# ex_05.net
KiCad netlist of a schematic drawn in EAGLE
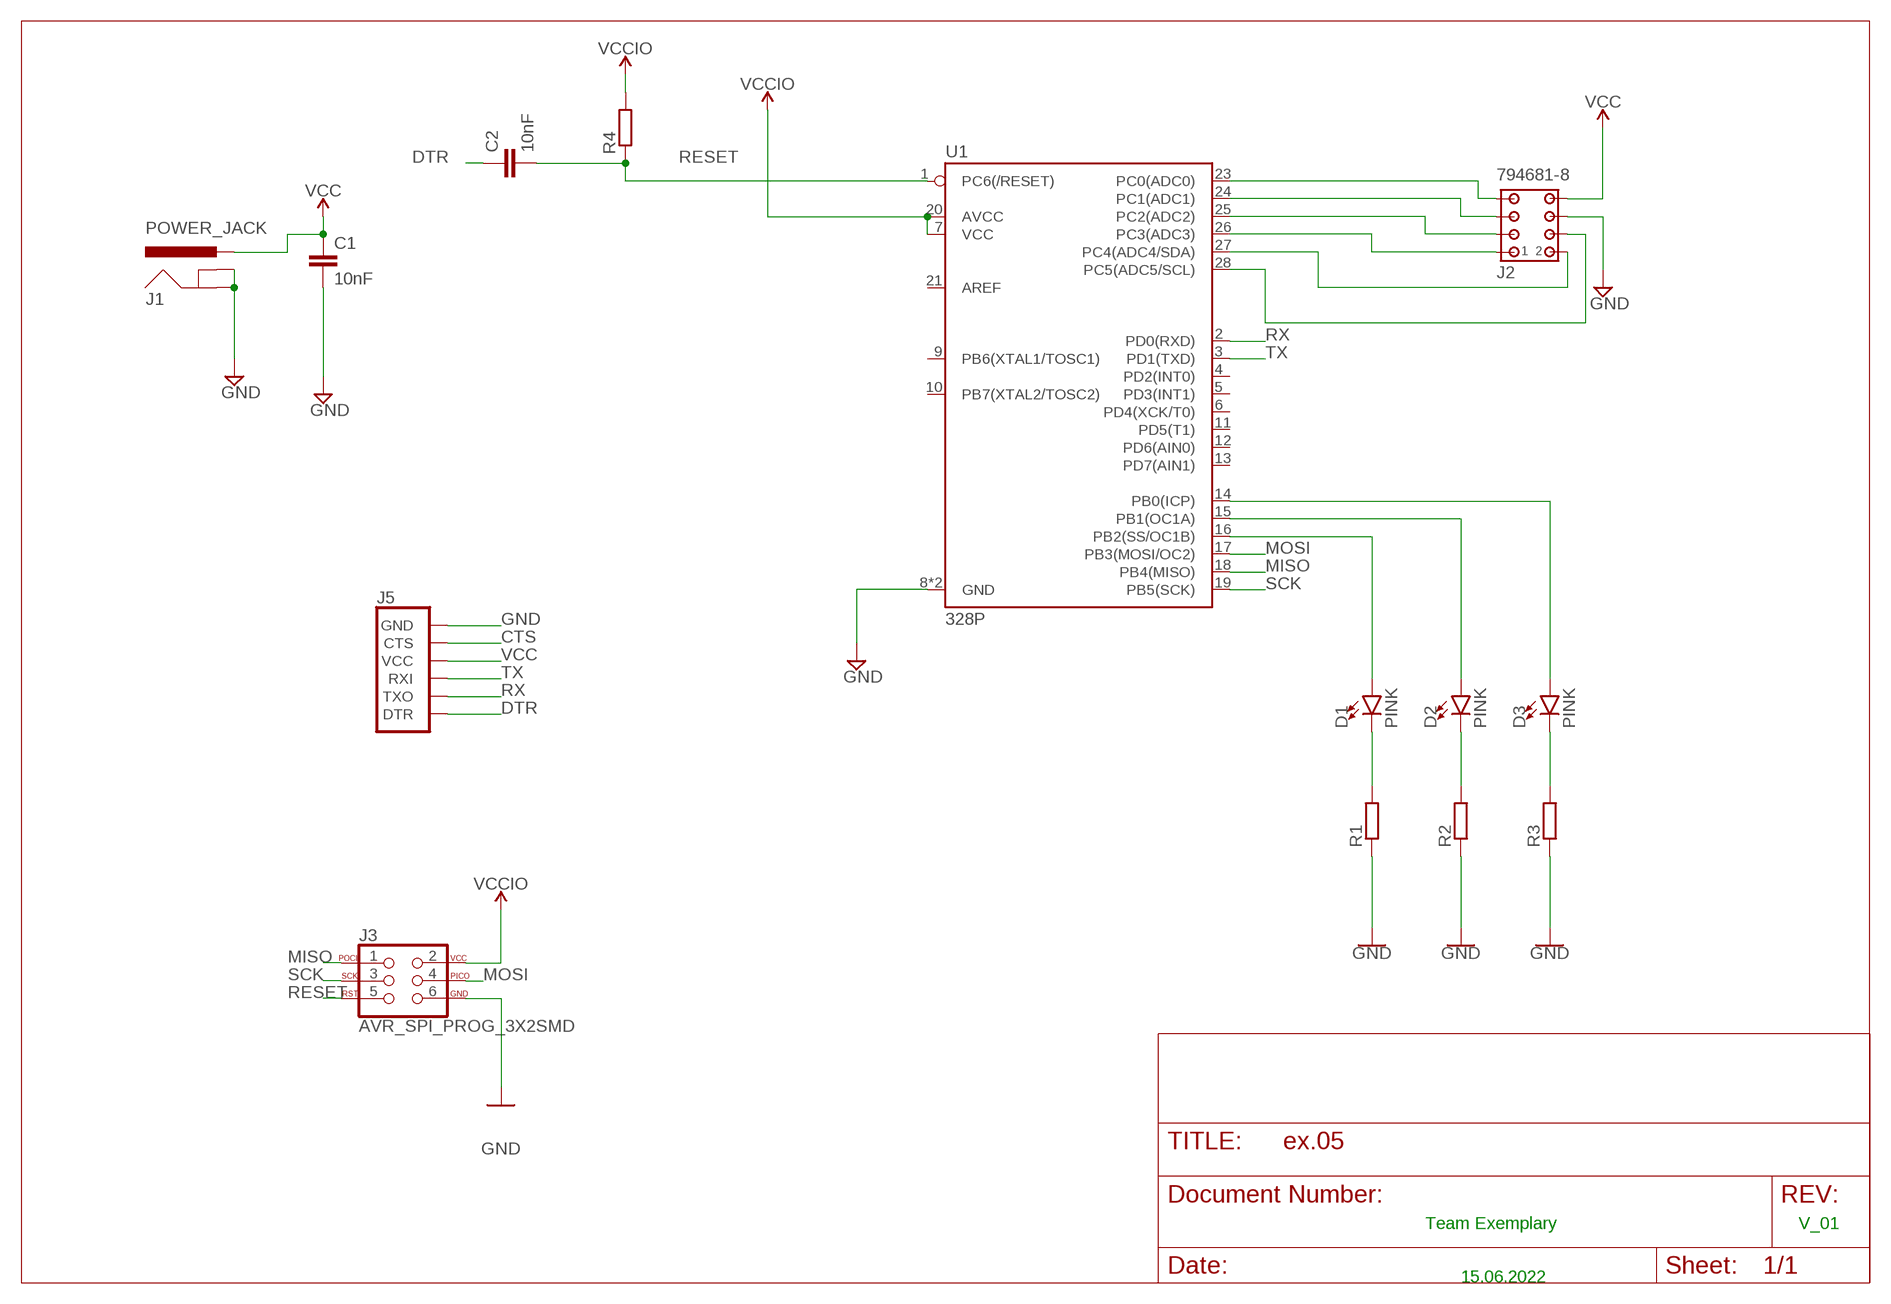
[diagram p0: schematic, sheet 1]

(export (version "E")
  (design (tool "Eeschema 10.0.6"))
  (components
    (comp (ref "C1")
      (value "10nF")
      (footprint "eagle-import:CAP-PTH-10MM")
      (libsource (lib "eagle-import") (part "10NF-PTH-10MM-10000V-1-%"))
    )
    (comp (ref "C2")
      (value "10nF")
      (footprint "eagle-import:CAP-PTH-10MM")
      (libsource (lib "eagle-import") (part "10NF-PTH-10MM-10000V-1-%"))
    )
    (comp (ref "D1")
      (value "PINK")
      (footprint "eagle-import:LED-1206")
      (libsource (lib "eagle-import") (part "LED-PINK1206"))
    )
    (comp (ref "D2")
      (value "PINK")
      (footprint "eagle-import:LED-1206")
      (libsource (lib "eagle-import") (part "LED-PINK1206"))
    )
    (comp (ref "D3")
      (value "PINK")
      (footprint "eagle-import:LED-1206")
      (libsource (lib "eagle-import") (part "LED-PINK1206"))
    )
    (comp (ref "J1")
      (value "POWER_JACK")
      (footprint "eagle-import:POWER_JACK_PTH")
      (libsource (lib "eagle-import") (part "POWER_JACK"))
    )
    (comp (ref "J2")
      (value "794681-8")
      (footprint "eagle-import:794681-8")
      (libsource (lib "eagle-import") (part "794681-8"))
    )
    (comp (ref "J3")
      (value "AVR_SPI_PROG_3X2SMD")
      (footprint "eagle-import:2X3_SMT_POSTS")
      (libsource (lib "eagle-import") (part "AVR_SPI_PROG_3X2SMD"))
    )
    (comp (ref "J5")
      (value "6_PIN_SERIAL_TARGETLOCK")
      (footprint "eagle-import:1X06_LOCK")
      (libsource (lib "eagle-import") (part "6_PIN_SERIAL_TARGETLOCK"))
    )
    (comp (ref "R1")
      (value "PMD")
      (footprint "eagle-import:PMD")
      (libsource (lib "eagle-import") (part "PMD"))
    )
    (comp (ref "R2")
      (value "PMD")
      (footprint "eagle-import:PMD")
      (libsource (lib "eagle-import") (part "PMD"))
    )
    (comp (ref "R3")
      (value "PMD")
      (footprint "eagle-import:PMD")
      (libsource (lib "eagle-import") (part "PMD"))
    )
    (comp (ref "R4")
      (value "PMD")
      (footprint "eagle-import:PMD")
      (libsource (lib "eagle-import") (part "PMD"))
    )
    (comp (ref "U1")
      (value "328P")
      (footprint "eagle-import:DIP28")
      (libsource (lib "eagle-import") (part "ATMEGA328P_PDIP"))
    )
  )
  (nets
    (net (code "1") (name "/CTS") (class "Default")
      (node (ref "J5") (pin "5") (pinfunction "CTS_5") (pintype "passive"))
    )
    (net (code "2") (name "/DTR") (class "Default")
      (node (ref "C2") (pin "1") (pinfunction "1_1") (pintype "passive"))
      (node (ref "J5") (pin "1") (pinfunction "DTR_1") (pintype "passive"))
    )
    (net (code "3") (name "/MISO") (class "Default")
      (node (ref "J3") (pin "1") (pinfunction "1_1") (pintype "passive"))
      (node (ref "U1") (pin "18") (pinfunction "PB4(MISO)_18") (pintype "bidirectional"))
    )
    (net (code "4") (name "/MOSI") (class "Default")
      (node (ref "J3") (pin "4") (pinfunction "4_4") (pintype "passive"))
      (node (ref "U1") (pin "17") (pinfunction "PB3(MOSI/OC2)_17") (pintype "bidirectional"))
    )
    (net (code "5") (name "/RESET") (class "Default")
      (node (ref "C2") (pin "2") (pinfunction "2_2") (pintype "passive"))
      (node (ref "J3") (pin "5") (pinfunction "5_5") (pintype "passive"))
      (node (ref "R4") (pin "2") (pinfunction "2_2") (pintype "passive"))
      (node (ref "U1") (pin "1") (pinfunction "PC6(/RESET)_1") (pintype "bidirectional"))
    )
    (net (code "6") (name "/RX") (class "Default")
      (node (ref "J5") (pin "3") (pinfunction "TXO_3") (pintype "passive"))
      (node (ref "U1") (pin "2") (pinfunction "PD0(RXD)_2") (pintype "bidirectional"))
    )
    (net (code "7") (name "/SCK") (class "Default")
      (node (ref "J3") (pin "3") (pinfunction "3_3") (pintype "passive"))
      (node (ref "U1") (pin "19") (pinfunction "PB5(SCK)_19") (pintype "bidirectional"))
    )
    (net (code "8") (name "/TX") (class "Default")
      (node (ref "J5") (pin "2") (pinfunction "RXI_2") (pintype "passive"))
      (node (ref "U1") (pin "3") (pinfunction "PD1(TXD)_3") (pintype "bidirectional"))
    )
    (net (code "9") (name "GND") (class "Default")
      (node (ref "C1") (pin "2") (pinfunction "2_2") (pintype "passive"))
      (node (ref "J1") (pin "GND") (pinfunction "GND_GND") (pintype "bidirectional"))
      (node (ref "J1") (pin "GNDBREAK") (pinfunction "GNDBREAK_GNDBREAK") (pintype "bidirectional"))
      (node (ref "J2") (pin "6") (pinfunction "6_6") (pintype "passive"))
      (node (ref "J3") (pin "6") (pinfunction "6_6") (pintype "passive"))
      (node (ref "J5") (pin "6") (pinfunction "GND_6") (pintype "passive"))
      (node (ref "R1") (pin "2") (pinfunction "2_2") (pintype "passive"))
      (node (ref "R2") (pin "2") (pinfunction "2_2") (pintype "passive"))
      (node (ref "R3") (pin "2") (pinfunction "2_2") (pintype "passive"))
      (node (ref "U1") (pin "22") (pinfunction "GND_22") (pintype "bidirectional"))
      (node (ref "U1") (pin "8") (pinfunction "GND_8") (pintype "bidirectional"))
    )
    (net (code "10") (name "Net-(D1-PadC)") (class "Default")
      (node (ref "D1") (pin "C") (pinfunction "C_C") (pintype "passive"))
      (node (ref "R1") (pin "1") (pinfunction "1_1") (pintype "passive"))
    )
    (net (code "11") (name "Net-(D2-PadC)") (class "Default")
      (node (ref "D2") (pin "C") (pinfunction "C_C") (pintype "passive"))
      (node (ref "R2") (pin "1") (pinfunction "1_1") (pintype "passive"))
    )
    (net (code "12") (name "Net-(D3-PadC)") (class "Default")
      (node (ref "D3") (pin "C") (pinfunction "C_C") (pintype "passive"))
      (node (ref "R3") (pin "1") (pinfunction "1_1") (pintype "passive"))
    )
    (net (code "13") (name "Net-(U1-PB0(ICP))") (class "Default")
      (node (ref "D3") (pin "A") (pinfunction "A_A") (pintype "passive"))
      (node (ref "U1") (pin "14") (pinfunction "PB0(ICP)_14") (pintype "bidirectional"))
    )
    (net (code "14") (name "Net-(U1-PB1(OC1A))") (class "Default")
      (node (ref "D2") (pin "A") (pinfunction "A_A") (pintype "passive"))
      (node (ref "U1") (pin "15") (pinfunction "PB1(OC1A)_15") (pintype "bidirectional"))
    )
    (net (code "15") (name "Net-(U1-PB2(SS{slash}OC1B))") (class "Default")
      (node (ref "D1") (pin "A") (pinfunction "A_A") (pintype "passive"))
      (node (ref "U1") (pin "16") (pinfunction "PB2(SS/OC1B)_16") (pintype "bidirectional"))
    )
    (net (code "16") (name "Net-(U1-PC0(ADC0))") (class "Default")
      (node (ref "J2") (pin "7") (pinfunction "7_7") (pintype "passive"))
      (node (ref "U1") (pin "23") (pinfunction "PC0(ADC0)_23") (pintype "bidirectional"))
    )
    (net (code "17") (name "Net-(U1-PC1(ADC1))") (class "Default")
      (node (ref "J2") (pin "5") (pinfunction "5_5") (pintype "passive"))
      (node (ref "U1") (pin "24") (pinfunction "PC1(ADC1)_24") (pintype "bidirectional"))
    )
    (net (code "18") (name "Net-(U1-PC2(ADC2))") (class "Default")
      (node (ref "J2") (pin "3") (pinfunction "3_3") (pintype "passive"))
      (node (ref "U1") (pin "25") (pinfunction "PC2(ADC2)_25") (pintype "bidirectional"))
    )
    (net (code "19") (name "Net-(U1-PC3(ADC3))") (class "Default")
      (node (ref "J2") (pin "1") (pinfunction "1_1") (pintype "passive"))
      (node (ref "U1") (pin "26") (pinfunction "PC3(ADC3)_26") (pintype "bidirectional"))
    )
    (net (code "20") (name "Net-(U1-PC4(ADC4{slash}SDA))") (class "Default")
      (node (ref "J2") (pin "2") (pinfunction "2_2") (pintype "passive"))
      (node (ref "U1") (pin "27") (pinfunction "PC4(ADC4/SDA)_27") (pintype "bidirectional"))
    )
    (net (code "21") (name "Net-(U1-PC5(ADC5{slash}SCL))") (class "Default")
      (node (ref "J2") (pin "4") (pinfunction "4_4") (pintype "passive"))
      (node (ref "U1") (pin "28") (pinfunction "PC5(ADC5/SCL)_28") (pintype "bidirectional"))
    )
    (net (code "22") (name "VCC") (class "Default")
      (node (ref "C1") (pin "1") (pinfunction "1_1") (pintype "passive"))
      (node (ref "J1") (pin "PWR") (pinfunction "PWR_PWR") (pintype "bidirectional"))
      (node (ref "J2") (pin "8") (pinfunction "8_8") (pintype "passive"))
      (node (ref "J5") (pin "4") (pinfunction "VCC_4") (pintype "passive"))
    )
    (net (code "23") (name "VCCIO") (class "Default")
      (node (ref "J3") (pin "2") (pinfunction "2_2") (pintype "passive"))
      (node (ref "R4") (pin "1") (pinfunction "1_1") (pintype "passive"))
      (node (ref "U1") (pin "20") (pinfunction "AVCC_20") (pintype "bidirectional"))
      (node (ref "U1") (pin "7") (pinfunction "VCC_7") (pintype "bidirectional"))
    )
    (net (code "24") (name "unconnected-(U1-AREF-Pad21)") (class "Default")
      (node (ref "U1") (pin "21") (pinfunction "AREF_21") (pintype "bidirectional"))
    )
    (net (code "25") (name "unconnected-(U1-PB6(XTAL1{slash}TOSC1)-Pad9)") (class "Default")
      (node (ref "U1") (pin "9") (pinfunction "PB6(XTAL1/TOSC1)_9") (pintype "bidirectional"))
    )
    (net (code "26") (name "unconnected-(U1-PB7(XTAL2{slash}TOSC2)-Pad10)") (class "Default")
      (node (ref "U1") (pin "10") (pinfunction "PB7(XTAL2/TOSC2)_10") (pintype "bidirectional"))
    )
    (net (code "27") (name "unconnected-(U1-PD2(INT0)-Pad4)") (class "Default")
      (node (ref "U1") (pin "4") (pinfunction "PD2(INT0)_4") (pintype "bidirectional"))
    )
    (net (code "28") (name "unconnected-(U1-PD3(INT1)-Pad5)") (class "Default")
      (node (ref "U1") (pin "5") (pinfunction "PD3(INT1)_5") (pintype "bidirectional"))
    )
    (net (code "29") (name "unconnected-(U1-PD4(XCK{slash}T0)-Pad6)") (class "Default")
      (node (ref "U1") (pin "6") (pinfunction "PD4(XCK/T0)_6") (pintype "bidirectional"))
    )
    (net (code "30") (name "unconnected-(U1-PD5(T1)-Pad11)") (class "Default")
      (node (ref "U1") (pin "11") (pinfunction "PD5(T1)_11") (pintype "bidirectional"))
    )
    (net (code "31") (name "unconnected-(U1-PD6(AIN0)-Pad12)") (class "Default")
      (node (ref "U1") (pin "12") (pinfunction "PD6(AIN0)_12") (pintype "bidirectional"))
    )
    (net (code "32") (name "unconnected-(U1-PD7(AIN1)-Pad13)") (class "Default")
      (node (ref "U1") (pin "13") (pinfunction "PD7(AIN1)_13") (pintype "bidirectional"))
    )
  )
)
